# Sensor_Glove_Sensors-X01.net
KiCad netlist of a schematic drawn in Altium Designer
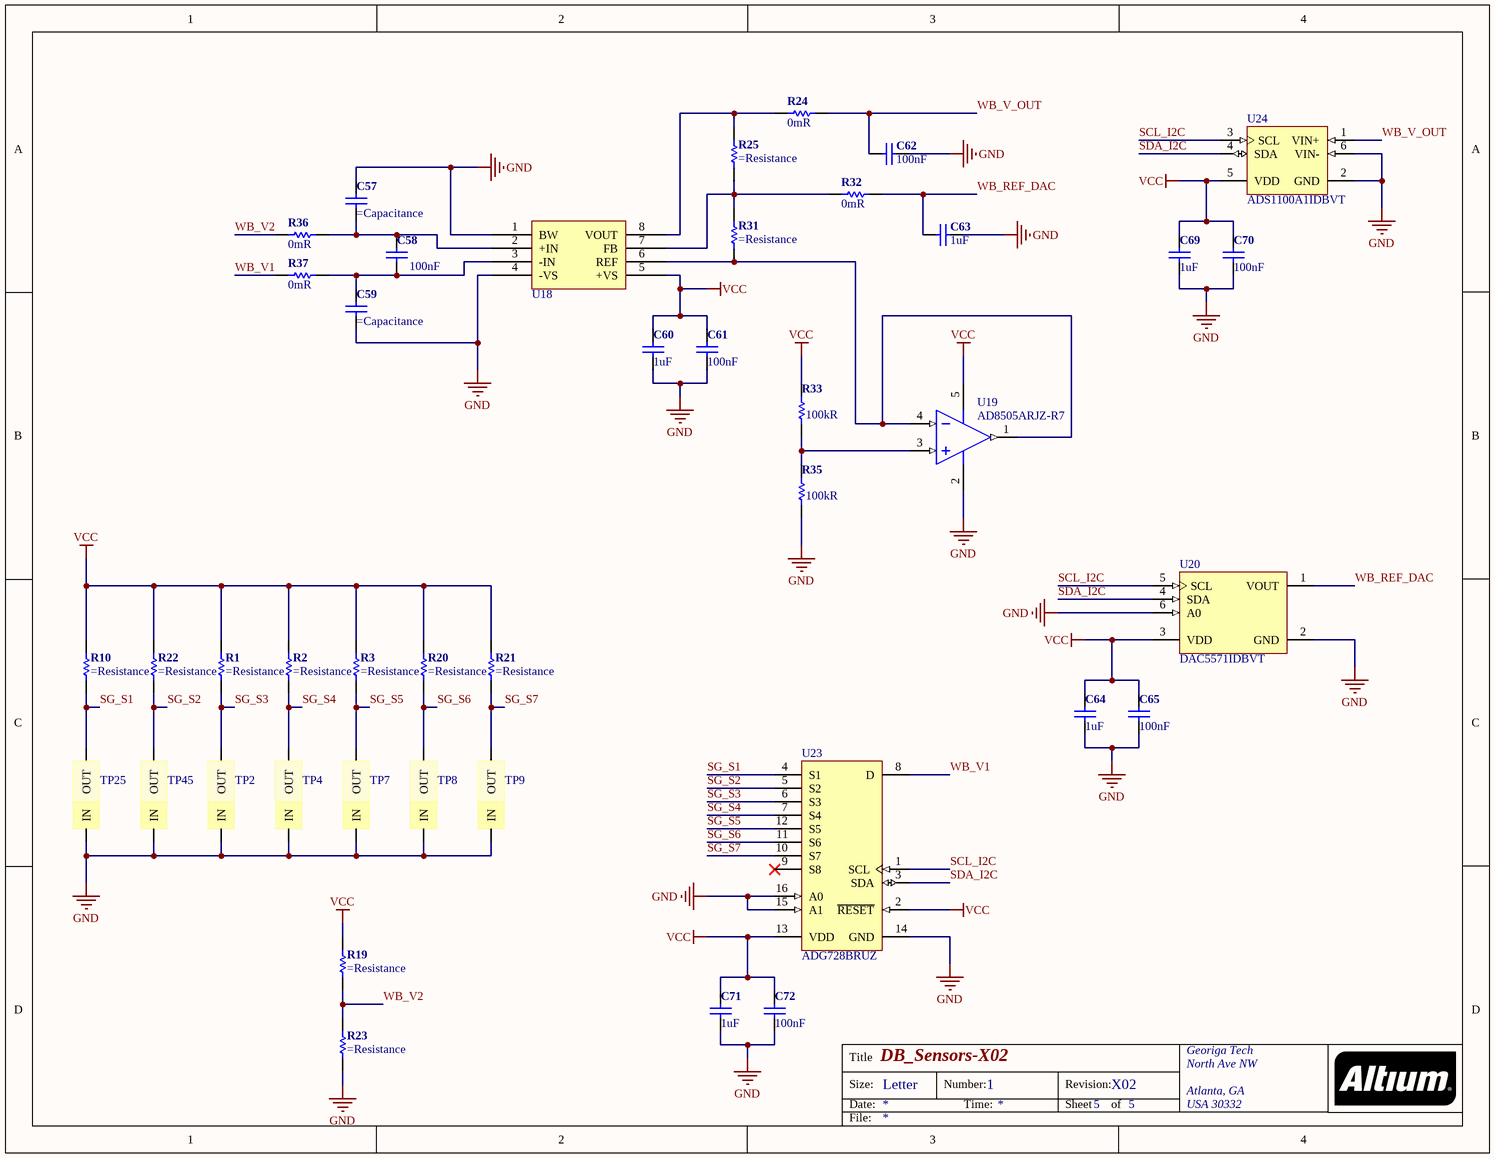
[diagram p0: Sensor_Glove_Sensors-X01.SchDoc]

(export (version "E")
  (design (tool "Eeschema 10.0.6"))
  (components
    (comp (ref "C57")
      (value "~")
      (footprint "C0402")
      (description "___ OHM ___ mW 0402(1005) SMD")
      (libsource (lib "DB-X02") (part "C-0402(1005)"))
    )
    (comp (ref "C58")
      (value "100nF")
      (footprint "C0402")
      (fields
        (field (name "MANUFACTURER") "Taiyo Yuden")
        (field (name "MANUFACTURER PART NUMBER") "TMK105BJ104KV-F")
        (field (name "TOLERANCE") "10%")
      )
      (libsource (lib "DB-X02") (part "C-0402(1005)"))
    )
    (comp (ref "C59")
      (value "~")
      (footprint "C0402")
      (description "___ OHM ___ mW 0402(1005) SMD")
      (libsource (lib "DB-X02") (part "C-0402(1005)"))
    )
    (comp (ref "C60")
      (value "1uF")
      (footprint "C0402")
      (fields
        (field (name "MANUFACTURER") "Yageo")
        (field (name "MANUFACTURER PART NUMBER") "CC0402MRX5R5BB105")
        (field (name "TOLERANCE") "20%")
      )
      (libsource (lib "DB-X02") (part "C-0402(1005)"))
    )
    (comp (ref "C61")
      (value "100nF")
      (footprint "C0402")
      (fields
        (field (name "MANUFACTURER") "Taiyo Yuden")
        (field (name "MANUFACTURER PART NUMBER") "TMK105BJ104KV-F")
        (field (name "TOLERANCE") "10%")
      )
      (libsource (lib "DB-X02") (part "C-0402(1005)"))
    )
    (comp (ref "C62")
      (value "100nF")
      (footprint "C0402")
      (fields
        (field (name "MANUFACTURER") "Taiyo Yuden")
        (field (name "MANUFACTURER PART NUMBER") "TMK105BJ104KV-F")
        (field (name "TOLERANCE") "10%")
      )
      (libsource (lib "DB-X02") (part "C-0402(1005)"))
    )
    (comp (ref "C63")
      (value "1uF")
      (footprint "C0402")
      (fields
        (field (name "MANUFACTURER") "Yageo")
        (field (name "MANUFACTURER PART NUMBER") "CC0402MRX5R5BB105")
        (field (name "TOLERANCE") "20%")
      )
      (libsource (lib "DB-X02") (part "C-0402(1005)"))
    )
    (comp (ref "C64")
      (value "1uF")
      (footprint "C0402")
      (fields
        (field (name "MANUFACTURER") "Yageo")
        (field (name "MANUFACTURER PART NUMBER") "CC0402MRX5R5BB105")
        (field (name "TOLERANCE") "20%")
      )
      (libsource (lib "DB-X02") (part "C-0402(1005)"))
    )
    (comp (ref "C65")
      (value "100nF")
      (footprint "C0402")
      (fields
        (field (name "MANUFACTURER") "Taiyo Yuden")
        (field (name "MANUFACTURER PART NUMBER") "TMK105BJ104KV-F")
        (field (name "TOLERANCE") "10%")
      )
      (libsource (lib "DB-X02") (part "C-0402(1005)"))
    )
    (comp (ref "C69")
      (value "1uF")
      (footprint "C0402")
      (fields
        (field (name "MANUFACTURER") "Yageo")
        (field (name "MANUFACTURER PART NUMBER") "CC0402MRX5R5BB105")
        (field (name "TOLERANCE") "20%")
      )
      (libsource (lib "DB-X02") (part "C-0402(1005)"))
    )
    (comp (ref "C70")
      (value "100nF")
      (footprint "C0402")
      (fields
        (field (name "MANUFACTURER") "Taiyo Yuden")
        (field (name "MANUFACTURER PART NUMBER") "TMK105BJ104KV-F")
        (field (name "TOLERANCE") "10%")
      )
      (libsource (lib "DB-X02") (part "C-0402(1005)"))
    )
    (comp (ref "C71")
      (value "1uF")
      (footprint "C0402")
      (fields
        (field (name "MANUFACTURER") "Yageo")
        (field (name "MANUFACTURER PART NUMBER") "CC0402MRX5R5BB105")
        (field (name "TOLERANCE") "20%")
      )
      (libsource (lib "DB-X02") (part "C-0402(1005)"))
    )
    (comp (ref "C72")
      (value "100nF")
      (footprint "C0402")
      (fields
        (field (name "MANUFACTURER") "Taiyo Yuden")
        (field (name "MANUFACTURER PART NUMBER") "TMK105BJ104KV-F")
        (field (name "TOLERANCE") "10%")
      )
      (libsource (lib "DB-X02") (part "C-0402(1005)"))
    )
    (comp (ref "R1")
      (value "~")
      (footprint "R0402")
      (description "___ OHM ___ mW 0402(1005) SMD")
      (libsource (lib "DB-X02") (part "R-0402(1005)"))
    )
    (comp (ref "R2")
      (value "~")
      (footprint "R0402")
      (description "___ OHM ___ mW 0402(1005) SMD")
      (libsource (lib "DB-X02") (part "R-0402(1005)"))
    )
    (comp (ref "R3")
      (value "~")
      (footprint "R0402")
      (description "___ OHM ___ mW 0402(1005) SMD")
      (libsource (lib "DB-X02") (part "R-0402(1005)"))
    )
    (comp (ref "R10")
      (value "~")
      (footprint "R0402")
      (description "___ OHM ___ mW 0402(1005) SMD")
      (libsource (lib "DB-X02") (part "R-0402(1005)"))
    )
    (comp (ref "R19")
      (value "~")
      (footprint "R0402")
      (description "___ OHM ___ mW 0402(1005) SMD")
      (libsource (lib "DB-X02") (part "R-0402(1005)"))
    )
    (comp (ref "R20")
      (value "~")
      (footprint "R0402")
      (description "___ OHM ___ mW 0402(1005) SMD")
      (libsource (lib "DB-X02") (part "R-0402(1005)"))
    )
    (comp (ref "R21")
      (value "~")
      (footprint "R0402")
      (description "___ OHM ___ mW 0402(1005) SMD")
      (libsource (lib "DB-X02") (part "R-0402(1005)"))
    )
    (comp (ref "R22")
      (value "~")
      (footprint "R0402")
      (description "___ OHM ___ mW 0402(1005) SMD")
      (libsource (lib "DB-X02") (part "R-0402(1005)"))
    )
    (comp (ref "R23")
      (value "~")
      (footprint "R0402")
      (description "___ OHM ___ mW 0402(1005) SMD")
      (libsource (lib "DB-X02") (part "R-0402(1005)"))
    )
    (comp (ref "R24")
      (value "0mR")
      (footprint "R0402")
      (description "Fixed Resistor, Metal Glaze/thick Film, 0.0625W, 0ohm, Surface Mount, 0402")
      (fields
        (field (name "MANUFACTURER") "Yageo")
        (field (name "MANUFACTURER PART NUMBER") "AC0402JR-070RL")
      )
      (libsource (lib "DB-X02") (part "R-0402(1005)"))
    )
    (comp (ref "R25")
      (value "~")
      (footprint "R0402")
      (description "___ OHM ___ mW 0402(1005) SMD")
      (libsource (lib "DB-X02") (part "R-0402(1005)"))
    )
    (comp (ref "R31")
      (value "~")
      (footprint "R0402")
      (description "___ OHM ___ mW 0402(1005) SMD")
      (libsource (lib "DB-X02") (part "R-0402(1005)"))
    )
    (comp (ref "R32")
      (value "0mR")
      (footprint "R0402")
      (description "Fixed Resistor, Metal Glaze/thick Film, 0.0625W, 0ohm, Surface Mount, 0402")
      (fields
        (field (name "MANUFACTURER") "Yageo")
        (field (name "MANUFACTURER PART NUMBER") "AC0402JR-070RL")
      )
      (libsource (lib "DB-X02") (part "R-0402(1005)"))
    )
    (comp (ref "R33")
      (value "100kR")
      (footprint "R0402")
      (fields
        (field (name "MANUFACTURER") "Yageo")
        (field (name "MANUFACTURER PART NUMBER") "AC0402FR-07100KL")
        (field (name "TOLERANCE") "1%")
      )
      (libsource (lib "DB-X02") (part "R-0402(1005)"))
    )
    (comp (ref "R35")
      (value "100kR")
      (footprint "R0402")
      (fields
        (field (name "MANUFACTURER") "Yageo")
        (field (name "MANUFACTURER PART NUMBER") "AC0402FR-07100KL")
        (field (name "TOLERANCE") "1%")
      )
      (libsource (lib "DB-X02") (part "R-0402(1005)"))
    )
    (comp (ref "R36")
      (value "0mR")
      (footprint "R0402")
      (description "Fixed Resistor, Metal Glaze/thick Film, 0.0625W, 0ohm, Surface Mount, 0402")
      (fields
        (field (name "MANUFACTURER") "Yageo")
        (field (name "MANUFACTURER PART NUMBER") "AC0402JR-070RL")
      )
      (libsource (lib "DB-X02") (part "R-0402(1005)"))
    )
    (comp (ref "R37")
      (value "0mR")
      (footprint "R0402")
      (description "Fixed Resistor, Metal Glaze/thick Film, 0.0625W, 0ohm, Surface Mount, 0402")
      (fields
        (field (name "MANUFACTURER") "Yageo")
        (field (name "MANUFACTURER PART NUMBER") "AC0402JR-070RL")
      )
      (libsource (lib "DB-X02") (part "R-0402(1005)"))
    )
    (comp (ref "TP2")
      (value "JUMPER")
      (footprint "JUMPER")
      (description "SHUNT LP W/HANDLE 2 POS 30AU")
      (fields
        (field (name "MANUFACTURER") "TE Connectivity")
        (field (name "MANUFACTURER PART NUMBER") "8815452")
      )
      (libsource (lib "DB-X02") (part "JUMPER"))
    )
    (comp (ref "TP4")
      (value "JUMPER")
      (footprint "JUMPER")
      (description "SHUNT LP W/HANDLE 2 POS 30AU")
      (fields
        (field (name "MANUFACTURER") "TE Connectivity")
        (field (name "MANUFACTURER PART NUMBER") "8815452")
      )
      (libsource (lib "DB-X02") (part "JUMPER"))
    )
    (comp (ref "TP7")
      (value "JUMPER")
      (footprint "JUMPER")
      (description "SHUNT LP W/HANDLE 2 POS 30AU")
      (fields
        (field (name "MANUFACTURER") "TE Connectivity")
        (field (name "MANUFACTURER PART NUMBER") "8815452")
      )
      (libsource (lib "DB-X02") (part "JUMPER"))
    )
    (comp (ref "TP8")
      (value "JUMPER")
      (footprint "JUMPER")
      (description "SHUNT LP W/HANDLE 2 POS 30AU")
      (fields
        (field (name "MANUFACTURER") "TE Connectivity")
        (field (name "MANUFACTURER PART NUMBER") "8815452")
      )
      (libsource (lib "DB-X02") (part "JUMPER"))
    )
    (comp (ref "TP9")
      (value "JUMPER")
      (footprint "JUMPER")
      (description "SHUNT LP W/HANDLE 2 POS 30AU")
      (fields
        (field (name "MANUFACTURER") "TE Connectivity")
        (field (name "MANUFACTURER PART NUMBER") "8815452")
      )
      (libsource (lib "DB-X02") (part "JUMPER"))
    )
    (comp (ref "TP25")
      (value "JUMPER")
      (footprint "JUMPER")
      (description "SHUNT LP W/HANDLE 2 POS 30AU")
      (fields
        (field (name "MANUFACTURER") "TE Connectivity")
        (field (name "MANUFACTURER PART NUMBER") "8815452")
      )
      (libsource (lib "DB-X02") (part "JUMPER"))
    )
    (comp (ref "TP45")
      (value "JUMPER")
      (footprint "JUMPER")
      (description "SHUNT LP W/HANDLE 2 POS 30AU")
      (fields
        (field (name "MANUFACTURER") "TE Connectivity")
        (field (name "MANUFACTURER PART NUMBER") "8815452")
      )
      (libsource (lib "DB-X02") (part "JUMPER"))
    )
    (comp (ref "U18")
      (value "Instrumentation Amplifier")
      (footprint "8-MSOP")
      (description "Instrumentation Amplifier, 1 Func, 75uV Offset-Max, 0.2MHz Band Width, CMOS, PDSO8")
      (fields
        (field (name "MANUFACTURER") "Analog Devices")
        (field (name "MANUFACTURER PART NUMBER") "AD8237ARMZ-R7")
      )
      (libsource (lib "DB-X02") (part "AD8237"))
    )
    (comp (ref "U19")
      (value "AD8505ARJZ-R7")
      (footprint "ADI-RJ-5_N")
      (fields (field (name "MANUFACTURER") "Analog Devices"))
      (libsource (lib "Altium Content Vault") (part "ADI-ADxxxx-X-5"))
    )
    (comp (ref "U20")
      (value "DAC5571IDBVT")
      (footprint "TI-DBV6_M")
      (fields (field (name "MANUFACTURER") "Texas Instruments"))
      (libsource (lib "Altium Content Vault") (part "TI-DACX571DBV6"))
    )
    (comp (ref "U23")
      (value "ADG728BRUZ")
      (footprint "ADI-RU-16_M")
      (fields (field (name "MANUFACTURER") "Analog Devices"))
      (libsource (lib "Altium Content Vault") (part "ADI-ADG728-RU-16"))
    )
    (comp (ref "U24")
      (value "ADS1100A1IDBVT")
      (footprint "TI-DBV6_N")
      (description "Self-Calibrating, 16-Bit ADC, -40 to 85 degC, 6-pin SOT23 (DBV6), Green (RoHS & no Sb/Br)")
      (fields (field (name "MANUFACTURER") "Texas Instruments"))
      (libsource (lib "Altium Content Vault") (part "TI-ADS1XX0XDBV6"))
    )
  )
  (nets
    (net (code "1") (name "/SCL_I2C") (class "Default")
      (node (ref "U20") (pin "5") (pinfunction "SCL_5") (pintype "input"))
      (node (ref "U23") (pin "1") (pinfunction "SCL_1") (pintype "input"))
      (node (ref "U24") (pin "3") (pinfunction "SCL_3") (pintype "input"))
    )
    (net (code "2") (name "/SDA_I2C") (class "Default")
      (node (ref "U20") (pin "4") (pinfunction "SDA_4") (pintype "input"))
      (node (ref "U23") (pin "3") (pinfunction "SDA_3") (pintype "bidirectional"))
      (node (ref "U24") (pin "4") (pinfunction "SDA_4") (pintype "bidirectional"))
    )
    (net (code "3") (name "/SG_S1") (class "Default")
      (node (ref "R10") (pin "2") (pinfunction "2_2") (pintype "passive"))
      (node (ref "TP25") (pin "2") (pinfunction "OUT_2") (pintype "passive"))
      (node (ref "U23") (pin "4") (pinfunction "S1_4") (pintype "passive"))
    )
    (net (code "4") (name "/SG_S2") (class "Default")
      (node (ref "R22") (pin "2") (pinfunction "2_2") (pintype "passive"))
      (node (ref "TP45") (pin "2") (pinfunction "OUT_2") (pintype "passive"))
      (node (ref "U23") (pin "5") (pinfunction "S2_5") (pintype "passive"))
    )
    (net (code "5") (name "/SG_S3") (class "Default")
      (node (ref "R1") (pin "2") (pinfunction "2_2") (pintype "passive"))
      (node (ref "TP2") (pin "2") (pinfunction "OUT_2") (pintype "passive"))
      (node (ref "U23") (pin "6") (pinfunction "S3_6") (pintype "passive"))
    )
    (net (code "6") (name "/SG_S4") (class "Default")
      (node (ref "R2") (pin "2") (pinfunction "2_2") (pintype "passive"))
      (node (ref "TP4") (pin "2") (pinfunction "OUT_2") (pintype "passive"))
      (node (ref "U23") (pin "7") (pinfunction "S4_7") (pintype "passive"))
    )
    (net (code "7") (name "/SG_S5") (class "Default")
      (node (ref "R3") (pin "2") (pinfunction "2_2") (pintype "passive"))
      (node (ref "TP7") (pin "2") (pinfunction "OUT_2") (pintype "passive"))
      (node (ref "U23") (pin "12") (pinfunction "S5_12") (pintype "passive"))
    )
    (net (code "8") (name "/SG_S6") (class "Default")
      (node (ref "R20") (pin "2") (pinfunction "2_2") (pintype "passive"))
      (node (ref "TP8") (pin "2") (pinfunction "OUT_2") (pintype "passive"))
      (node (ref "U23") (pin "11") (pinfunction "S6_11") (pintype "passive"))
    )
    (net (code "9") (name "/SG_S7") (class "Default")
      (node (ref "R21") (pin "2") (pinfunction "2_2") (pintype "passive"))
      (node (ref "TP9") (pin "2") (pinfunction "OUT_2") (pintype "passive"))
      (node (ref "U23") (pin "10") (pinfunction "S7_10") (pintype "passive"))
    )
    (net (code "10") (name "/WB_REF_DAC") (class "Default")
      (node (ref "C63") (pin "1") (pinfunction "1_1") (pintype "passive"))
      (node (ref "R32") (pin "2") (pinfunction "2_2") (pintype "passive"))
      (node (ref "U20") (pin "1") (pinfunction "VOUT_1") (pintype "tri_state"))
    )
    (net (code "11") (name "/WB_V1") (class "Default")
      (node (ref "R37") (pin "1") (pinfunction "1_1") (pintype "passive"))
      (node (ref "U23") (pin "8") (pinfunction "D_8") (pintype "passive"))
    )
    (net (code "12") (name "/WB_V2") (class "Default")
      (node (ref "R19") (pin "2") (pinfunction "2_2") (pintype "passive"))
      (node (ref "R23") (pin "1") (pinfunction "1_1") (pintype "passive"))
      (node (ref "R36") (pin "1") (pinfunction "1_1") (pintype "passive"))
    )
    (net (code "13") (name "/WB_V_OUT") (class "Default")
      (node (ref "C62") (pin "1") (pinfunction "1_1") (pintype "passive"))
      (node (ref "R24") (pin "2") (pinfunction "2_2") (pintype "passive"))
      (node (ref "U24") (pin "1") (pinfunction "VIN+_1") (pintype "input"))
    )
    (net (code "14") (name "GND") (class "Default")
      (node (ref "C57") (pin "1") (pinfunction "1_1") (pintype "passive"))
      (node (ref "C59") (pin "2") (pinfunction "2_2") (pintype "passive"))
      (node (ref "C60") (pin "2") (pinfunction "2_2") (pintype "passive"))
      (node (ref "C61") (pin "2") (pinfunction "2_2") (pintype "passive"))
      (node (ref "C62") (pin "2") (pinfunction "2_2") (pintype "passive"))
      (node (ref "C63") (pin "2") (pinfunction "2_2") (pintype "passive"))
      (node (ref "C64") (pin "2") (pinfunction "2_2") (pintype "passive"))
      (node (ref "C65") (pin "2") (pinfunction "2_2") (pintype "passive"))
      (node (ref "C69") (pin "2") (pinfunction "2_2") (pintype "passive"))
      (node (ref "C70") (pin "2") (pinfunction "2_2") (pintype "passive"))
      (node (ref "C71") (pin "2") (pinfunction "2_2") (pintype "passive"))
      (node (ref "C72") (pin "2") (pinfunction "2_2") (pintype "passive"))
      (node (ref "R23") (pin "2") (pinfunction "2_2") (pintype "passive"))
      (node (ref "R35") (pin "2") (pinfunction "2_2") (pintype "passive"))
      (node (ref "TP2") (pin "1") (pinfunction "IN_1") (pintype "passive"))
      (node (ref "TP25") (pin "1") (pinfunction "IN_1") (pintype "passive"))
      (node (ref "TP4") (pin "1") (pinfunction "IN_1") (pintype "passive"))
      (node (ref "TP45") (pin "1") (pinfunction "IN_1") (pintype "passive"))
      (node (ref "TP7") (pin "1") (pinfunction "IN_1") (pintype "passive"))
      (node (ref "TP8") (pin "1") (pinfunction "IN_1") (pintype "passive"))
      (node (ref "TP9") (pin "1") (pinfunction "IN_1") (pintype "passive"))
      (node (ref "U18") (pin "1") (pinfunction "BW_1") (pintype "passive"))
      (node (ref "U18") (pin "4") (pinfunction "-VS_4") (pintype "passive"))
      (node (ref "U19") (pin "2") (pinfunction "-V_2") (pintype "power_in"))
      (node (ref "U20") (pin "2") (pinfunction "GND_2") (pintype "power_in"))
      (node (ref "U20") (pin "6") (pinfunction "A0_6") (pintype "input"))
      (node (ref "U23") (pin "14") (pinfunction "GND_14") (pintype "power_in"))
      (node (ref "U23") (pin "15") (pinfunction "A1_15") (pintype "input"))
      (node (ref "U23") (pin "16") (pinfunction "A0_16") (pintype "input"))
      (node (ref "U24") (pin "2") (pinfunction "GND_2") (pintype "power_in"))
      (node (ref "U24") (pin "6") (pinfunction "VIN-_6") (pintype "input"))
    )
    (net (code "15") (name "Net-(U18-+IN)") (class "Default")
      (node (ref "C57") (pin "2") (pinfunction "2_2") (pintype "passive"))
      (node (ref "C58") (pin "1") (pinfunction "1_1") (pintype "passive"))
      (node (ref "R36") (pin "2") (pinfunction "2_2") (pintype "passive"))
      (node (ref "U18") (pin "2") (pinfunction "+IN_2") (pintype "passive"))
    )
    (net (code "16") (name "Net-(U18--IN)") (class "Default")
      (node (ref "C58") (pin "2") (pinfunction "2_2") (pintype "passive"))
      (node (ref "C59") (pin "1") (pinfunction "1_1") (pintype "passive"))
      (node (ref "R37") (pin "2") (pinfunction "2_2") (pintype "passive"))
      (node (ref "U18") (pin "3") (pinfunction "-IN_3") (pintype "passive"))
    )
    (net (code "17") (name "Net-(U18-FB)") (class "Default")
      (node (ref "R25") (pin "1") (pinfunction "1_1") (pintype "passive"))
      (node (ref "R31") (pin "2") (pinfunction "2_2") (pintype "passive"))
      (node (ref "R32") (pin "1") (pinfunction "1_1") (pintype "passive"))
      (node (ref "U18") (pin "7") (pinfunction "FB_7") (pintype "passive"))
    )
    (net (code "18") (name "Net-(U18-REF)") (class "Default")
      (node (ref "R31") (pin "1") (pinfunction "1_1") (pintype "passive"))
      (node (ref "U18") (pin "6") (pinfunction "REF_6") (pintype "passive"))
      (node (ref "U19") (pin "1") (pinfunction "OUT_1") (pintype "output"))
      (node (ref "U19") (pin "4") (pinfunction "-IN_4") (pintype "input"))
    )
    (net (code "19") (name "Net-(U18-VOUT)") (class "Default")
      (node (ref "R24") (pin "1") (pinfunction "1_1") (pintype "passive"))
      (node (ref "R25") (pin "2") (pinfunction "2_2") (pintype "passive"))
      (node (ref "U18") (pin "8") (pinfunction "VOUT_8") (pintype "passive"))
    )
    (net (code "20") (name "Net-(U19-+IN)") (class "Default")
      (node (ref "R33") (pin "2") (pinfunction "2_2") (pintype "passive"))
      (node (ref "R35") (pin "1") (pinfunction "1_1") (pintype "passive"))
      (node (ref "U19") (pin "3") (pinfunction "+IN_3") (pintype "input"))
    )
    (net (code "21") (name "VCC") (class "Default")
      (node (ref "C60") (pin "1") (pinfunction "1_1") (pintype "passive"))
      (node (ref "C61") (pin "1") (pinfunction "1_1") (pintype "passive"))
      (node (ref "C64") (pin "1") (pinfunction "1_1") (pintype "passive"))
      (node (ref "C65") (pin "1") (pinfunction "1_1") (pintype "passive"))
      (node (ref "C69") (pin "1") (pinfunction "1_1") (pintype "passive"))
      (node (ref "C70") (pin "1") (pinfunction "1_1") (pintype "passive"))
      (node (ref "C71") (pin "1") (pinfunction "1_1") (pintype "passive"))
      (node (ref "C72") (pin "1") (pinfunction "1_1") (pintype "passive"))
      (node (ref "R1") (pin "1") (pinfunction "1_1") (pintype "passive"))
      (node (ref "R10") (pin "1") (pinfunction "1_1") (pintype "passive"))
      (node (ref "R19") (pin "1") (pinfunction "1_1") (pintype "passive"))
      (node (ref "R2") (pin "1") (pinfunction "1_1") (pintype "passive"))
      (node (ref "R20") (pin "1") (pinfunction "1_1") (pintype "passive"))
      (node (ref "R21") (pin "1") (pinfunction "1_1") (pintype "passive"))
      (node (ref "R22") (pin "1") (pinfunction "1_1") (pintype "passive"))
      (node (ref "R3") (pin "1") (pinfunction "1_1") (pintype "passive"))
      (node (ref "R33") (pin "1") (pinfunction "1_1") (pintype "passive"))
      (node (ref "U18") (pin "5") (pinfunction "+VS_5") (pintype "passive"))
      (node (ref "U19") (pin "5") (pinfunction "+V_5") (pintype "power_in"))
      (node (ref "U20") (pin "3") (pinfunction "VDD_3") (pintype "power_in"))
      (node (ref "U23") (pin "13") (pinfunction "VDD_13") (pintype "power_in"))
      (node (ref "U23") (pin "2") (pinfunction "~{RESET}_2") (pintype "input"))
      (node (ref "U24") (pin "5") (pinfunction "VDD_5") (pintype "power_in"))
    )
    (net (code "22") (name "unconnected-(U23-S8-Pad9)") (class "Default")
      (node (ref "U23") (pin "9") (pinfunction "S8_9") (pintype "passive+no_connect"))
    )
  )
)
